# Audio_Flash_eeprom.net
KiCad netlist of a schematic drawn in Altium Designer
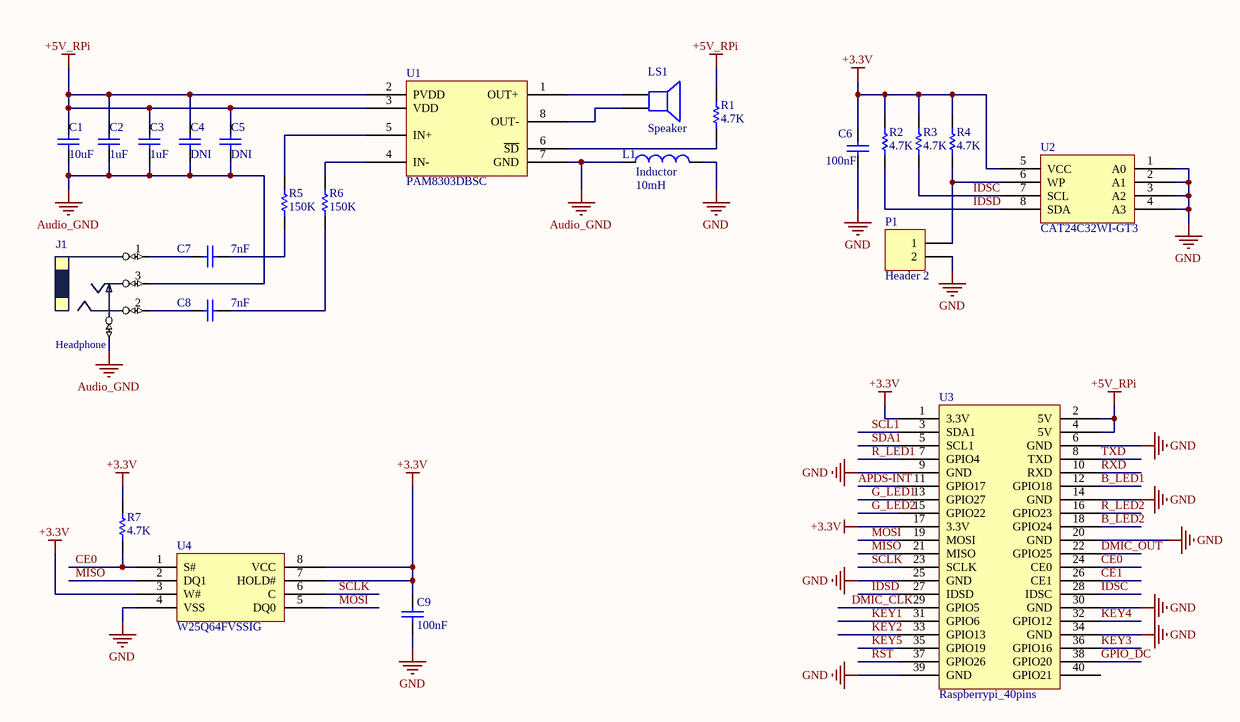
[diagram p0: Audio_Flash_eeprom.SchDoc]

(export (version "E")
  (design (tool "Eeschema 10.0.6"))
  (components
    (comp (ref "C1")
      (value "10uF")
      (footprint "C0603")
      (description "Capacitor (Semiconductor SIM Model)")
      (fields (field (name "PUBLISHER") "Altium Limited"))
      (libsource (lib "Miscellaneous Devices") (part "Cap Semi"))
    )
    (comp (ref "C2")
      (value "1uF")
      (footprint "C0603")
      (description "Capacitor (Semiconductor SIM Model)")
      (fields (field (name "PUBLISHER") "Altium Limited"))
      (libsource (lib "Miscellaneous Devices") (part "Cap Semi"))
    )
    (comp (ref "C3")
      (value "1uF")
      (footprint "C0603")
      (description "Capacitor (Semiconductor SIM Model)")
      (fields (field (name "PUBLISHER") "Altium Limited"))
      (libsource (lib "Miscellaneous Devices") (part "Cap Semi"))
    )
    (comp (ref "C4")
      (value "DNI")
      (footprint "C0603")
      (description "Capacitor (Semiconductor SIM Model)")
      (fields (field (name "PUBLISHER") "Altium Limited"))
      (libsource (lib "Miscellaneous Devices") (part "Cap Semi"))
    )
    (comp (ref "C5")
      (value "DNI")
      (footprint "C0603")
      (description "Capacitor (Semiconductor SIM Model)")
      (fields (field (name "PUBLISHER") "Altium Limited"))
      (libsource (lib "Miscellaneous Devices") (part "Cap Semi"))
    )
    (comp (ref "C6")
      (value "100nF")
      (footprint "C0603")
      (description "Capacitor (Semiconductor SIM Model)")
      (fields (field (name "PUBLISHER") "Altium Limited"))
      (libsource (lib "Miscellaneous Devices") (part "Cap Semi"))
    )
    (comp (ref "C7")
      (value "7nF")
      (footprint "C0603")
      (description "Capacitor (Semiconductor SIM Model)")
      (fields (field (name "PUBLISHER") "Altium Limited"))
      (libsource (lib "Miscellaneous Devices") (part "Cap Semi"))
    )
    (comp (ref "C8")
      (value "7nF")
      (footprint "C0603")
      (description "Capacitor (Semiconductor SIM Model)")
      (fields (field (name "PUBLISHER") "Altium Limited"))
      (libsource (lib "Miscellaneous Devices") (part "Cap Semi"))
    )
    (comp (ref "C9")
      (value "100nF")
      (footprint "C0603")
      (description "Capacitor")
      (fields (field (name "PUBLISHER") "Altium Limited"))
      (libsource (lib "Miscellaneous Devices") (part "Cap"))
    )
    (comp (ref "J1") (value "Headphone") (footprint "AudioJack") (libsource (lib "*") (part "PHONEJACK1")))
    (comp (ref "L1")
      (value "Inductor")
      (footprint "C0603")
      (fields (field (name "ALTIUM_VALUE") "10mH") (field (name "PUBLISHER") "Altium Limited"))
      (libsource (lib "Miscellaneous Devices") (part "Inductor"))
    )
    (comp (ref "LS1")
      (value "Speaker")
      (footprint "Speaker")
      (description "Loudspeaker")
      (fields (field (name "PUBLISHER") "Altium Limited"))
      (libsource (lib "Miscellaneous Devices") (part "Speaker"))
    )
    (comp (ref "P1")
      (value "Header 2")
      (footprint "HDR1X2")
      (description "Header, 2-Pin")
      (fields (field (name "PUBLISHER") "Altium Limited"))
      (libsource (lib "Miscellaneous Connectors") (part "Header 2"))
    )
    (comp (ref "R1")
      (value "4.7K")
      (footprint "R0603")
      (description "Resistor")
      (fields (field (name "PUBLISHER") "Altium Limited"))
      (libsource (lib "Miscellaneous Devices") (part "Res1"))
    )
    (comp (ref "R2")
      (value "4.7K")
      (footprint "R0603")
      (description "Resistor")
      (fields (field (name "PUBLISHER") "Altium Limited"))
      (libsource (lib "Miscellaneous Devices") (part "Res1"))
    )
    (comp (ref "R3")
      (value "4.7K")
      (footprint "R0603")
      (description "Resistor")
      (fields (field (name "PUBLISHER") "Altium Limited"))
      (libsource (lib "Miscellaneous Devices") (part "Res1"))
    )
    (comp (ref "R4")
      (value "4.7K")
      (footprint "R0603")
      (description "Resistor")
      (fields (field (name "PUBLISHER") "Altium Limited"))
      (libsource (lib "Miscellaneous Devices") (part "Res1"))
    )
    (comp (ref "R5")
      (value "150K")
      (footprint "R0603")
      (description "Resistor")
      (fields (field (name "PUBLISHER") "Altium Limited"))
      (libsource (lib "Miscellaneous Devices") (part "Res1"))
    )
    (comp (ref "R6")
      (value "150K")
      (footprint "R0603")
      (description "Resistor")
      (fields (field (name "PUBLISHER") "Altium Limited"))
      (libsource (lib "Miscellaneous Devices") (part "Res1"))
    )
    (comp (ref "R7")
      (value "4.7K")
      (footprint "R0603")
      (description "Resistor")
      (fields (field (name "PUBLISHER") "Altium Limited"))
      (libsource (lib "Miscellaneous Devices") (part "Res1"))
    )
    (comp (ref "U1")
      (value "PAM8303DBSC")
      (footprint "MSOP8")
      (libsource (lib "RaspberryPi_Hat_schlib") (part "PAM8303D"))
    )
    (comp (ref "U2")
      (value "CAT24C32WI-GT3")
      (footprint "SOP-8")
      (description "Raspiberry Config EEProm")
      (libsource (lib "RaspberryPi_Hat_schlib") (part "CAT24C32WI-GT3"))
    )
    (comp (ref "U3")
      (value "Raspberrypi_40pins")
      (footprint "SMT_2*20_2.54")
      (description "树莓派40pin管脚")
      (libsource (lib "RaspberryPi_Hat_schlib") (part "Raspberrypi_40pins"))
    )
    (comp (ref "U4")
      (value "W25Q64FVSSIG")
      (footprint "SOIC8")
      (libsource (lib "STEP-CYC10-SOC") (part "M25P32-VMW6TG"))
    )
  )
  (nets
    (net (code "1") (name "+3.3V") (class "Default")
      (node (ref "C6") (pin "2") (pinfunction "2_2") (pintype "passive"))
      (node (ref "C9") (pin "2") (pinfunction "2_2") (pintype "passive"))
      (node (ref "R2") (pin "2") (pinfunction "2_2") (pintype "passive"))
      (node (ref "R3") (pin "2") (pinfunction "2_2") (pintype "passive"))
      (node (ref "R4") (pin "2") (pinfunction "2_2") (pintype "passive"))
      (node (ref "R7") (pin "2") (pinfunction "2_2") (pintype "passive"))
      (node (ref "U2") (pin "5") (pinfunction "VCC_5") (pintype "passive"))
      (node (ref "U3") (pin "1") (pinfunction "3.3V_1") (pintype "passive"))
      (node (ref "U3") (pin "17") (pinfunction "3.3V_17") (pintype "passive"))
      (node (ref "U4") (pin "3") (pinfunction "W#_3") (pintype "passive"))
      (node (ref "U4") (pin "7") (pinfunction "HOLD#_7") (pintype "passive"))
      (node (ref "U4") (pin "8") (pinfunction "VCC_8") (pintype "passive"))
    )
    (net (code "2") (name "+5V_RPi") (class "Default")
      (node (ref "C1") (pin "2") (pinfunction "2_2") (pintype "passive"))
      (node (ref "C2") (pin "2") (pinfunction "2_2") (pintype "passive"))
      (node (ref "C3") (pin "2") (pinfunction "2_2") (pintype "passive"))
      (node (ref "C4") (pin "2") (pinfunction "2_2") (pintype "passive"))
      (node (ref "C5") (pin "2") (pinfunction "2_2") (pintype "passive"))
      (node (ref "R1") (pin "2") (pinfunction "2_2") (pintype "passive"))
      (node (ref "U1") (pin "2") (pinfunction "PVDD_2") (pintype "passive"))
      (node (ref "U1") (pin "3") (pinfunction "VDD_3") (pintype "passive"))
      (node (ref "U3") (pin "2") (pinfunction "5V_2") (pintype "passive"))
      (node (ref "U3") (pin "4") (pinfunction "5V_4") (pintype "passive"))
    )
    (net (code "3") (name "/APDS-INT") (class "Default")
      (node (ref "U3") (pin "11") (pinfunction "GPIO17_11") (pintype "passive"))
    )
    (net (code "4") (name "/B_LED1") (class "Default")
      (node (ref "U3") (pin "12") (pinfunction "GPIO18_12") (pintype "passive"))
    )
    (net (code "5") (name "/B_LED2") (class "Default")
      (node (ref "U3") (pin "18") (pinfunction "GPIO24_18") (pintype "passive"))
    )
    (net (code "6") (name "/CE0") (class "Default")
      (node (ref "R7") (pin "1") (pinfunction "1_1") (pintype "passive"))
      (node (ref "U3") (pin "24") (pinfunction "CE0_24") (pintype "passive"))
      (node (ref "U4") (pin "1") (pinfunction "S#_1") (pintype "passive"))
    )
    (net (code "7") (name "/CE1") (class "Default")
      (node (ref "U3") (pin "26") (pinfunction "CE1_26") (pintype "passive"))
    )
    (net (code "8") (name "/DMIC_CLK") (class "Default")
      (node (ref "U3") (pin "29") (pinfunction "GPIO5_29") (pintype "passive"))
    )
    (net (code "9") (name "/DMIC_OUT") (class "Default")
      (node (ref "U3") (pin "22") (pinfunction "GPIO25_22") (pintype "passive"))
    )
    (net (code "10") (name "/GPIO_DC") (class "Default")
      (node (ref "U3") (pin "38") (pinfunction "GPIO20_38") (pintype "passive"))
    )
    (net (code "11") (name "/G_LED1") (class "Default")
      (node (ref "U3") (pin "13") (pinfunction "GPIO27_13") (pintype "passive"))
    )
    (net (code "12") (name "/G_LED2") (class "Default")
      (node (ref "U3") (pin "15") (pinfunction "GPIO22_15") (pintype "passive"))
    )
    (net (code "13") (name "/IDSC") (class "Default")
      (node (ref "R3") (pin "1") (pinfunction "1_1") (pintype "passive"))
      (node (ref "U2") (pin "7") (pinfunction "SCL_7") (pintype "passive"))
      (node (ref "U3") (pin "28") (pinfunction "IDSC_28") (pintype "passive"))
    )
    (net (code "14") (name "/IDSD") (class "Default")
      (node (ref "R2") (pin "1") (pinfunction "1_1") (pintype "passive"))
      (node (ref "U2") (pin "8") (pinfunction "SDA_8") (pintype "passive"))
      (node (ref "U3") (pin "27") (pinfunction "IDSD_27") (pintype "passive"))
    )
    (net (code "15") (name "/KEY1") (class "Default")
      (node (ref "U3") (pin "31") (pinfunction "GPIO6_31") (pintype "passive"))
    )
    (net (code "16") (name "/KEY2") (class "Default")
      (node (ref "U3") (pin "33") (pinfunction "GPIO13_33") (pintype "passive"))
    )
    (net (code "17") (name "/KEY3") (class "Default")
      (node (ref "U3") (pin "36") (pinfunction "GPIO16_36") (pintype "passive"))
    )
    (net (code "18") (name "/KEY4") (class "Default")
      (node (ref "U3") (pin "32") (pinfunction "GPIO12_32") (pintype "passive"))
    )
    (net (code "19") (name "/KEY5") (class "Default")
      (node (ref "U3") (pin "35") (pinfunction "GPIO19_35") (pintype "passive"))
    )
    (net (code "20") (name "/MISO") (class "Default")
      (node (ref "U3") (pin "21") (pinfunction "MISO_21") (pintype "passive"))
      (node (ref "U4") (pin "2") (pinfunction "DQ1_2") (pintype "passive"))
    )
    (net (code "21") (name "/MOSI") (class "Default")
      (node (ref "U3") (pin "19") (pinfunction "MOSI_19") (pintype "passive"))
      (node (ref "U4") (pin "5") (pinfunction "DQ0_5") (pintype "passive"))
    )
    (net (code "22") (name "/RST") (class "Default")
      (node (ref "U3") (pin "37") (pinfunction "GPIO26_37") (pintype "passive"))
    )
    (net (code "23") (name "/RXD") (class "Default")
      (node (ref "U3") (pin "10") (pinfunction "RXD_10") (pintype "passive"))
    )
    (net (code "24") (name "/R_LED1") (class "Default")
      (node (ref "U3") (pin "7") (pinfunction "GPIO4_7") (pintype "passive"))
    )
    (net (code "25") (name "/R_LED2") (class "Default")
      (node (ref "U3") (pin "16") (pinfunction "GPIO23_16") (pintype "passive"))
    )
    (net (code "26") (name "/SCL1") (class "Default")
      (node (ref "U3") (pin "3") (pinfunction "SDA1_3") (pintype "passive"))
    )
    (net (code "27") (name "/SCLK") (class "Default")
      (node (ref "U3") (pin "23") (pinfunction "SCLK_23") (pintype "passive"))
      (node (ref "U4") (pin "6") (pinfunction "C_6") (pintype "passive"))
    )
    (net (code "28") (name "/SDA1") (class "Default")
      (node (ref "U3") (pin "5") (pinfunction "SCL1_5") (pintype "passive"))
    )
    (net (code "29") (name "/TXD") (class "Default")
      (node (ref "U3") (pin "8") (pinfunction "TXD_8") (pintype "passive"))
    )
    (net (code "30") (name "Audio_GND") (class "Default")
      (node (ref "C1") (pin "1") (pinfunction "1_1") (pintype "passive"))
      (node (ref "C2") (pin "1") (pinfunction "1_1") (pintype "passive"))
      (node (ref "C3") (pin "1") (pinfunction "1_1") (pintype "passive"))
      (node (ref "C4") (pin "1") (pinfunction "1_1") (pintype "passive"))
      (node (ref "C5") (pin "1") (pinfunction "1_1") (pintype "passive"))
      (node (ref "J1") (pin "3") (pintype "bidirectional"))
      (node (ref "J1") (pin "4") (pintype "bidirectional"))
      (node (ref "L1") (pin "1") (pinfunction "1_1") (pintype "passive"))
      (node (ref "U1") (pin "7") (pinfunction "GND_7") (pintype "passive"))
    )
    (net (code "31") (name "GND") (class "Default")
      (node (ref "C6") (pin "1") (pinfunction "1_1") (pintype "passive"))
      (node (ref "C9") (pin "1") (pinfunction "1_1") (pintype "passive"))
      (node (ref "L1") (pin "2") (pinfunction "2_2") (pintype "passive"))
      (node (ref "P1") (pin "2") (pinfunction "2_2") (pintype "passive"))
      (node (ref "U2") (pin "1") (pinfunction "A0_1") (pintype "passive"))
      (node (ref "U2") (pin "2") (pinfunction "A1_2") (pintype "passive"))
      (node (ref "U2") (pin "3") (pinfunction "A2_3") (pintype "passive"))
      (node (ref "U2") (pin "4") (pinfunction "A3_4") (pintype "passive"))
      (node (ref "U3") (pin "14") (pinfunction "GND_14") (pintype "passive"))
      (node (ref "U3") (pin "20") (pinfunction "GND_20") (pintype "passive"))
      (node (ref "U3") (pin "25") (pinfunction "GND_25") (pintype "passive"))
      (node (ref "U3") (pin "30") (pinfunction "GND_30") (pintype "passive"))
      (node (ref "U3") (pin "34") (pinfunction "GND_34") (pintype "passive"))
      (node (ref "U3") (pin "39") (pinfunction "GND_39") (pintype "passive"))
      (node (ref "U3") (pin "6") (pinfunction "GND_6") (pintype "passive"))
      (node (ref "U3") (pin "9") (pinfunction "GND_9") (pintype "passive"))
      (node (ref "U4") (pin "4") (pinfunction "VSS_4") (pintype "passive"))
    )
    (net (code "32") (name "Net-(C7-Pad1)") (class "Default")
      (node (ref "C7") (pin "1") (pinfunction "1_1") (pintype "passive"))
      (node (ref "R5") (pin "2") (pinfunction "2_2") (pintype "passive"))
    )
    (net (code "33") (name "Net-(C8-Pad1)") (class "Default")
      (node (ref "C8") (pin "1") (pinfunction "1_1") (pintype "passive"))
      (node (ref "R6") (pin "2") (pinfunction "2_2") (pintype "passive"))
    )
    (net (code "34") (name "Net-(J1-L)") (class "Default")
      (node (ref "C7") (pin "2") (pinfunction "2_2") (pintype "passive"))
      (node (ref "J1") (pin "1") (pinfunction "L_1") (pintype "bidirectional"))
    )
    (net (code "35") (name "Net-(J1-R)") (class "Default")
      (node (ref "C8") (pin "2") (pinfunction "2_2") (pintype "passive"))
      (node (ref "J1") (pin "2") (pinfunction "R_2") (pintype "bidirectional"))
    )
    (net (code "36") (name "Net-(U1-IN+)") (class "Default")
      (node (ref "R5") (pin "1") (pinfunction "1_1") (pintype "passive"))
      (node (ref "U1") (pin "5") (pinfunction "IN+_5") (pintype "passive"))
    )
    (net (code "37") (name "Net-(U1-IN-)") (class "Default")
      (node (ref "R6") (pin "1") (pinfunction "1_1") (pintype "passive"))
      (node (ref "U1") (pin "4") (pinfunction "IN-_4") (pintype "passive"))
    )
    (net (code "38") (name "Net-(U1-OUT+)") (class "Default")
      (node (ref "LS1") (pin "1") (pinfunction "1_1") (pintype "passive"))
      (node (ref "U1") (pin "1") (pinfunction "OUT+_1") (pintype "passive"))
    )
    (net (code "39") (name "Net-(U1-OUT-)") (class "Default")
      (node (ref "LS1") (pin "2") (pinfunction "2_2") (pintype "passive"))
      (node (ref "U1") (pin "8") (pinfunction "OUT-_8") (pintype "passive"))
    )
    (net (code "40") (name "Net-(U1-~{SD})") (class "Default")
      (node (ref "R1") (pin "1") (pinfunction "1_1") (pintype "passive"))
      (node (ref "U1") (pin "6") (pinfunction "~{SD}_6") (pintype "passive"))
    )
    (net (code "41") (name "Net-(U2-WP)") (class "Default")
      (node (ref "P1") (pin "1") (pinfunction "1_1") (pintype "passive"))
      (node (ref "R4") (pin "1") (pinfunction "1_1") (pintype "passive"))
      (node (ref "U2") (pin "6") (pinfunction "WP_6") (pintype "passive"))
    )
    (net (code "42") (name "unconnected-(U3-GPIO21-Pad40)") (class "Default")
      (node (ref "U3") (pin "40") (pinfunction "GPIO21_40") (pintype "passive"))
    )
  )
)
